# input.net
KiCad netlist of a schematic drawn in Altium Designer
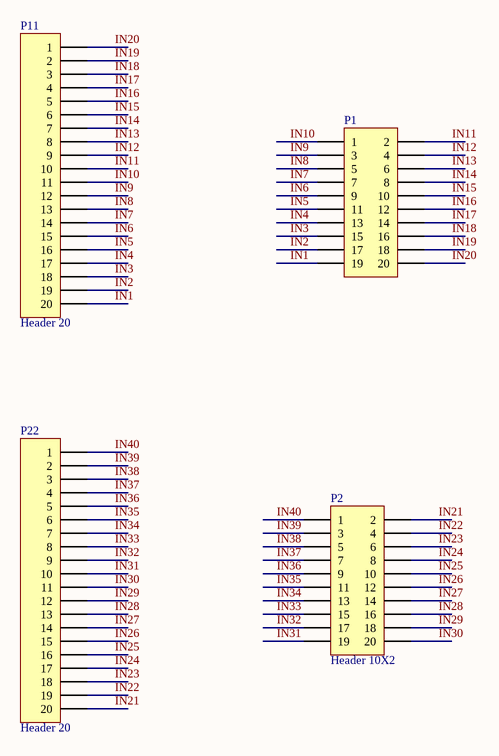
[diagram p0: input.SchDoc]

(export (version "E")
  (design (tool "Eeschema 10.0.6"))
  (components
    (comp (ref "P1")
      (value "Header 10X2")
      (footprint "HDR2X10")
      (description "Header, 10-Pin, Dual row")
      (fields (field (name "PUBLISHER") "Altium Limited"))
      (libsource (lib "Miscellaneous Connectors") (part "Header 10X2"))
    )
    (comp (ref "P2")
      (value "Header 10X2")
      (footprint "HDR2X10")
      (description "Header, 10-Pin, Dual row")
      (fields (field (name "PUBLISHER") "Altium Limited"))
      (libsource (lib "Miscellaneous Connectors") (part "Header 10X2"))
    )
    (comp (ref "P11")
      (value "Header 20")
      (footprint "HDR1X20")
      (description "Header, 20-Pin")
      (fields (field (name "PUBLISHER") "Altium Limited"))
      (libsource (lib "Miscellaneous Connectors") (part "Header 20"))
    )
    (comp (ref "P22")
      (value "Header 20")
      (footprint "HDR1X20")
      (description "Header, 20-Pin")
      (fields (field (name "PUBLISHER") "Altium Limited"))
      (libsource (lib "Miscellaneous Connectors") (part "Header 20"))
    )
  )
  (nets
    (net (code "1") (name "/IN1") (class "Default")
      (node (ref "P1") (pin "19") (pinfunction "19_19") (pintype "passive"))
      (node (ref "P11") (pin "20") (pinfunction "20_20") (pintype "passive"))
    )
    (net (code "2") (name "/IN2") (class "Default")
      (node (ref "P1") (pin "17") (pinfunction "17_17") (pintype "passive"))
      (node (ref "P11") (pin "19") (pinfunction "19_19") (pintype "passive"))
    )
    (net (code "3") (name "/IN3") (class "Default")
      (node (ref "P1") (pin "15") (pinfunction "15_15") (pintype "passive"))
      (node (ref "P11") (pin "18") (pinfunction "18_18") (pintype "passive"))
    )
    (net (code "4") (name "/IN4") (class "Default")
      (node (ref "P1") (pin "13") (pinfunction "13_13") (pintype "passive"))
      (node (ref "P11") (pin "17") (pinfunction "17_17") (pintype "passive"))
    )
    (net (code "5") (name "/IN5") (class "Default")
      (node (ref "P1") (pin "11") (pinfunction "11_11") (pintype "passive"))
      (node (ref "P11") (pin "16") (pinfunction "16_16") (pintype "passive"))
    )
    (net (code "6") (name "/IN6") (class "Default")
      (node (ref "P1") (pin "9") (pinfunction "9_9") (pintype "passive"))
      (node (ref "P11") (pin "15") (pinfunction "15_15") (pintype "passive"))
    )
    (net (code "7") (name "/IN7") (class "Default")
      (node (ref "P1") (pin "7") (pinfunction "7_7") (pintype "passive"))
      (node (ref "P11") (pin "14") (pinfunction "14_14") (pintype "passive"))
    )
    (net (code "8") (name "/IN8") (class "Default")
      (node (ref "P1") (pin "5") (pinfunction "5_5") (pintype "passive"))
      (node (ref "P11") (pin "13") (pinfunction "13_13") (pintype "passive"))
    )
    (net (code "9") (name "/IN9") (class "Default")
      (node (ref "P1") (pin "3") (pinfunction "3_3") (pintype "passive"))
      (node (ref "P11") (pin "12") (pinfunction "12_12") (pintype "passive"))
    )
    (net (code "10") (name "/IN10") (class "Default")
      (node (ref "P1") (pin "1") (pinfunction "1_1") (pintype "passive"))
      (node (ref "P11") (pin "11") (pinfunction "11_11") (pintype "passive"))
    )
    (net (code "11") (name "/IN11") (class "Default")
      (node (ref "P1") (pin "2") (pinfunction "2_2") (pintype "passive"))
      (node (ref "P11") (pin "10") (pinfunction "10_10") (pintype "passive"))
    )
    (net (code "12") (name "/IN12") (class "Default")
      (node (ref "P1") (pin "4") (pinfunction "4_4") (pintype "passive"))
      (node (ref "P11") (pin "9") (pinfunction "9_9") (pintype "passive"))
    )
    (net (code "13") (name "/IN13") (class "Default")
      (node (ref "P1") (pin "6") (pinfunction "6_6") (pintype "passive"))
      (node (ref "P11") (pin "8") (pinfunction "8_8") (pintype "passive"))
    )
    (net (code "14") (name "/IN14") (class "Default")
      (node (ref "P1") (pin "8") (pinfunction "8_8") (pintype "passive"))
      (node (ref "P11") (pin "7") (pinfunction "7_7") (pintype "passive"))
    )
    (net (code "15") (name "/IN15") (class "Default")
      (node (ref "P1") (pin "10") (pinfunction "10_10") (pintype "passive"))
      (node (ref "P11") (pin "6") (pinfunction "6_6") (pintype "passive"))
    )
    (net (code "16") (name "/IN16") (class "Default")
      (node (ref "P1") (pin "12") (pinfunction "12_12") (pintype "passive"))
      (node (ref "P11") (pin "5") (pinfunction "5_5") (pintype "passive"))
    )
    (net (code "17") (name "/IN17") (class "Default")
      (node (ref "P1") (pin "14") (pinfunction "14_14") (pintype "passive"))
      (node (ref "P11") (pin "4") (pinfunction "4_4") (pintype "passive"))
    )
    (net (code "18") (name "/IN18") (class "Default")
      (node (ref "P1") (pin "16") (pinfunction "16_16") (pintype "passive"))
      (node (ref "P11") (pin "3") (pinfunction "3_3") (pintype "passive"))
    )
    (net (code "19") (name "/IN19") (class "Default")
      (node (ref "P1") (pin "18") (pinfunction "18_18") (pintype "passive"))
      (node (ref "P11") (pin "2") (pinfunction "2_2") (pintype "passive"))
    )
    (net (code "20") (name "/IN20") (class "Default")
      (node (ref "P1") (pin "20") (pinfunction "20_20") (pintype "passive"))
      (node (ref "P11") (pin "1") (pinfunction "1_1") (pintype "passive"))
    )
    (net (code "21") (name "/IN21") (class "Default")
      (node (ref "P2") (pin "2") (pinfunction "2_2") (pintype "passive"))
      (node (ref "P22") (pin "20") (pinfunction "20_20") (pintype "passive"))
    )
    (net (code "22") (name "/IN22") (class "Default")
      (node (ref "P2") (pin "4") (pinfunction "4_4") (pintype "passive"))
      (node (ref "P22") (pin "19") (pinfunction "19_19") (pintype "passive"))
    )
    (net (code "23") (name "/IN23") (class "Default")
      (node (ref "P2") (pin "6") (pinfunction "6_6") (pintype "passive"))
      (node (ref "P22") (pin "18") (pinfunction "18_18") (pintype "passive"))
    )
    (net (code "24") (name "/IN24") (class "Default")
      (node (ref "P2") (pin "8") (pinfunction "8_8") (pintype "passive"))
      (node (ref "P22") (pin "17") (pinfunction "17_17") (pintype "passive"))
    )
    (net (code "25") (name "/IN25") (class "Default")
      (node (ref "P2") (pin "10") (pinfunction "10_10") (pintype "passive"))
      (node (ref "P22") (pin "16") (pinfunction "16_16") (pintype "passive"))
    )
    (net (code "26") (name "/IN26") (class "Default")
      (node (ref "P2") (pin "12") (pinfunction "12_12") (pintype "passive"))
      (node (ref "P22") (pin "15") (pinfunction "15_15") (pintype "passive"))
    )
    (net (code "27") (name "/IN27") (class "Default")
      (node (ref "P2") (pin "14") (pinfunction "14_14") (pintype "passive"))
      (node (ref "P22") (pin "14") (pinfunction "14_14") (pintype "passive"))
    )
    (net (code "28") (name "/IN28") (class "Default")
      (node (ref "P2") (pin "16") (pinfunction "16_16") (pintype "passive"))
      (node (ref "P22") (pin "13") (pinfunction "13_13") (pintype "passive"))
    )
    (net (code "29") (name "/IN29") (class "Default")
      (node (ref "P2") (pin "18") (pinfunction "18_18") (pintype "passive"))
      (node (ref "P22") (pin "12") (pinfunction "12_12") (pintype "passive"))
    )
    (net (code "30") (name "/IN30") (class "Default")
      (node (ref "P2") (pin "20") (pinfunction "20_20") (pintype "passive"))
      (node (ref "P22") (pin "11") (pinfunction "11_11") (pintype "passive"))
    )
    (net (code "31") (name "/IN31") (class "Default")
      (node (ref "P2") (pin "19") (pinfunction "19_19") (pintype "passive"))
      (node (ref "P22") (pin "10") (pinfunction "10_10") (pintype "passive"))
    )
    (net (code "32") (name "/IN32") (class "Default")
      (node (ref "P2") (pin "17") (pinfunction "17_17") (pintype "passive"))
      (node (ref "P22") (pin "9") (pinfunction "9_9") (pintype "passive"))
    )
    (net (code "33") (name "/IN33") (class "Default")
      (node (ref "P2") (pin "15") (pinfunction "15_15") (pintype "passive"))
      (node (ref "P22") (pin "8") (pinfunction "8_8") (pintype "passive"))
    )
    (net (code "34") (name "/IN34") (class "Default")
      (node (ref "P2") (pin "13") (pinfunction "13_13") (pintype "passive"))
      (node (ref "P22") (pin "7") (pinfunction "7_7") (pintype "passive"))
    )
    (net (code "35") (name "/IN35") (class "Default")
      (node (ref "P2") (pin "11") (pinfunction "11_11") (pintype "passive"))
      (node (ref "P22") (pin "6") (pinfunction "6_6") (pintype "passive"))
    )
    (net (code "36") (name "/IN36") (class "Default")
      (node (ref "P2") (pin "9") (pinfunction "9_9") (pintype "passive"))
      (node (ref "P22") (pin "5") (pinfunction "5_5") (pintype "passive"))
    )
    (net (code "37") (name "/IN37") (class "Default")
      (node (ref "P2") (pin "7") (pinfunction "7_7") (pintype "passive"))
      (node (ref "P22") (pin "4") (pinfunction "4_4") (pintype "passive"))
    )
    (net (code "38") (name "/IN38") (class "Default")
      (node (ref "P2") (pin "5") (pinfunction "5_5") (pintype "passive"))
      (node (ref "P22") (pin "3") (pinfunction "3_3") (pintype "passive"))
    )
    (net (code "39") (name "/IN39") (class "Default")
      (node (ref "P2") (pin "3") (pinfunction "3_3") (pintype "passive"))
      (node (ref "P22") (pin "2") (pinfunction "2_2") (pintype "passive"))
    )
    (net (code "40") (name "/IN40") (class "Default")
      (node (ref "P2") (pin "1") (pinfunction "1_1") (pintype "passive"))
      (node (ref "P22") (pin "1") (pinfunction "1_1") (pintype "passive"))
    )
  )
)
